# ear-o_mic_board.net
KiCad netlist of a schematic drawn in EAGLE
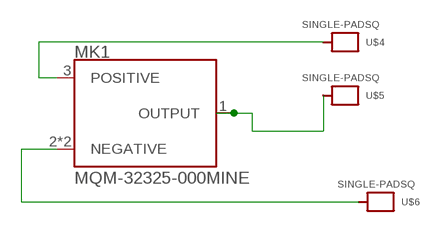
[diagram p0: schematic, sheet 1]

(export (version "E")
  (design (tool "Eeschema 10.0.6"))
  (components
    (comp (ref "MK1")
      (value "MQM-32325-000MINE")
      (footprint "eagle-import:MIC_MINE")
      (libsource (lib "eagle-import") (part "MQM-32325-000MINE"))
    )
    (comp (ref "U$4")
      (value "SINGLE-PADSQ")
      (footprint "eagle-import:SQUAREPAD0.8")
      (libsource (lib "eagle-import") (part "SINGLE-PADSQ"))
    )
    (comp (ref "U$5")
      (value "SINGLE-PADSQ")
      (footprint "eagle-import:SQUAREPAD0.8")
      (libsource (lib "eagle-import") (part "SINGLE-PADSQ"))
    )
    (comp (ref "U$6")
      (value "SINGLE-PADSQ")
      (footprint "eagle-import:SQUAREPAD0.8")
      (libsource (lib "eagle-import") (part "SINGLE-PADSQ"))
    )
  )
  (nets
    (net (code "1") (name "Net-(MK1-OUTPUT)") (class "Default")
      (node (ref "MK1") (pin "1") (pinfunction "OUTPUT_1") (pintype "output"))
      (node (ref "U$5") (pin "P$1") (pinfunction "1_P$1") (pintype "bidirectional"))
    )
    (net (code "2") (name "Net-(MK1-POSITIVE)") (class "Default")
      (node (ref "MK1") (pin "3") (pinfunction "POSITIVE_3") (pintype "input"))
      (node (ref "U$4") (pin "P$1") (pinfunction "1_P$1") (pintype "bidirectional"))
    )
    (net (code "3") (name "Net-(U$6-1)") (class "Default")
      (node (ref "MK1") (pin "2") (pinfunction "NEGATIVE_2") (pintype "input"))
      (node (ref "MK1") (pin "P$1") (pinfunction "NEGATIVE_P$1") (pintype "input"))
      (node (ref "U$6") (pin "P$1") (pinfunction "1_P$1") (pintype "bidirectional"))
    )
  )
)
